# design.net
KiCad netlist of a schematic drawn in Altium Designer
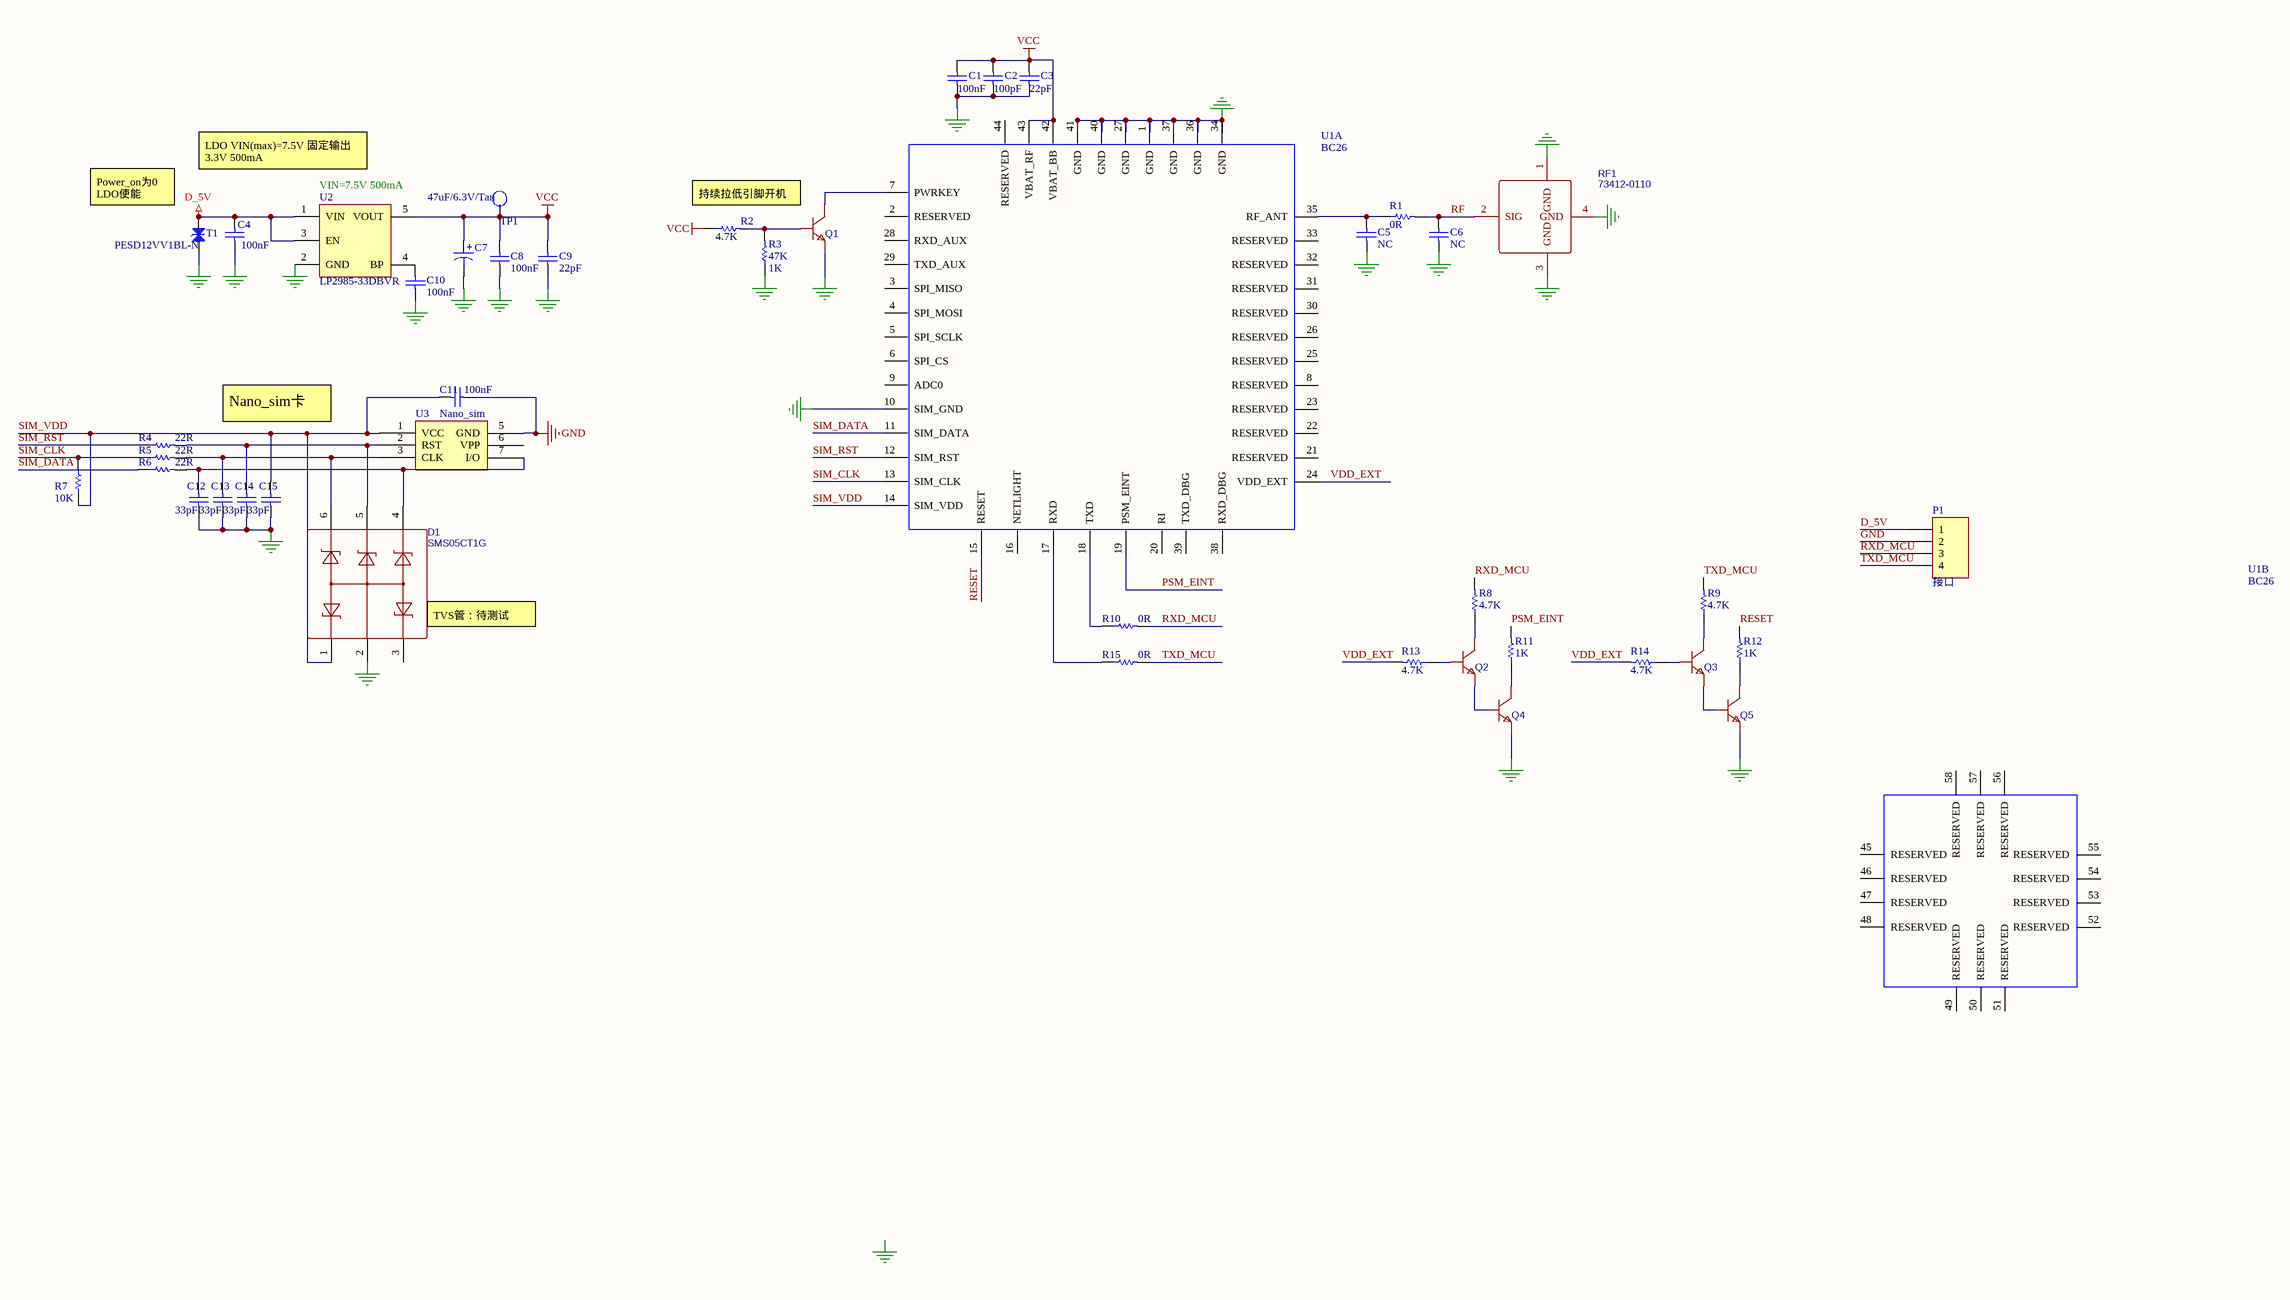
[diagram p0: 无线小样.SchDoc]

(export (version "E")
  (design (tool "Eeschema 10.0.6"))
  (components
    (comp (ref "C1")
      (value "100nF")
      (footprint "0402C")
      (description "Capacitor")
      (fields (field (name "PUBLISHER") "Altium Limited"))
      (libsource (lib "") (part "Cap_1"))
    )
    (comp (ref "C2")
      (value "100pF")
      (footprint "0402C")
      (description "Capacitor")
      (fields (field (name "PUBLISHER") "Altium Limited"))
      (libsource (lib "") (part "Cap_1"))
    )
    (comp (ref "C3")
      (value "22pF")
      (footprint "0402C")
      (description "Capacitor")
      (fields (field (name "PUBLISHER") "Altium Limited"))
      (libsource (lib "") (part "Cap_1"))
    )
    (comp (ref "C4")
      (value "100nF")
      (footprint "0402C")
      (description "Capacitor")
      (fields (field (name "PUBLISHER") "Altium Limited"))
      (libsource (lib "Miscellaneous Devices") (part "Cap"))
    )
    (comp (ref "C5")
      (value "NC")
      (footprint "0603C")
      (description "Capacitor")
      (fields (field (name "PUBLISHER") "Altium Limited"))
      (libsource (lib "") (part "Cap_1"))
    )
    (comp (ref "C6")
      (value "NC")
      (footprint "0603C")
      (description "Capacitor")
      (fields (field (name "PUBLISHER") "Altium Limited"))
      (libsource (lib "") (part "Cap_1"))
    )
    (comp (ref "C7")
      (value "47uF/6.3V/Tan")
      (footprint "0402C")
      (description "Polarized Capacitor (Radial)")
      (fields (field (name "PUBLISHER") "Altium Limited"))
      (libsource (lib "Miscellaneous Devices") (part "Cap Pol1"))
    )
    (comp (ref "C8")
      (value "100nF")
      (footprint "0402C")
      (description "Capacitor")
      (fields (field (name "PUBLISHER") "Altium Limited"))
      (libsource (lib "") (part "Cap_1"))
    )
    (comp (ref "C9")
      (value "22pF")
      (footprint "0402C")
      (description "Capacitor")
      (fields (field (name "PUBLISHER") "Altium Limited"))
      (libsource (lib "") (part "Cap_1"))
    )
    (comp (ref "C10")
      (value "100nF")
      (footprint "0402C")
      (description "Capacitor")
      (fields (field (name "PUBLISHER") "Altium Limited"))
      (libsource (lib "") (part "Cap_1"))
    )
    (comp (ref "C11")
      (value "100nF")
      (footprint "0402C")
      (description "Capacitor")
      (fields (field (name "PUBLISHER") "Altium Limited"))
      (libsource (lib "") (part "Cap_1"))
    )
    (comp (ref "C12")
      (value "33pF")
      (footprint "0402C")
      (description "Capacitor")
      (fields (field (name "PUBLISHER") "Altium Limited"))
      (libsource (lib "") (part "Cap_1"))
    )
    (comp (ref "C13")
      (value "33pF")
      (footprint "0402C")
      (description "Capacitor")
      (fields (field (name "PUBLISHER") "Altium Limited"))
      (libsource (lib "") (part "Cap_1"))
    )
    (comp (ref "C14")
      (value "33pF")
      (footprint "0402C")
      (description "Capacitor")
      (fields (field (name "PUBLISHER") "Altium Limited"))
      (libsource (lib "") (part "Cap_1"))
    )
    (comp (ref "C15")
      (value "33pF")
      (footprint "0402C")
      (description "Capacitor")
      (fields (field (name "PUBLISHER") "Altium Limited"))
      (libsource (lib "") (part "Cap_1"))
    )
    (comp (ref "D1")
      (value "SMS05CT1G")
      (footprint "TSOP-6_L3.0-W1.5-P0.95-LS2.8-BL")
      (fields (field (name "BOM_SUPPLIER PART") "C233427") (field (name "CONTRIBUTOR") "LCSC"))
      (libsource (lib "ESD") (part "SMS05CT1G"))
    )
    (comp (ref "P1")
      (value "接口")
      (footprint "HDR1X4")
      (description "Header, 4-Pin")
      (fields (field (name "PUBLISHER") "Altium Limited"))
      (libsource (lib "Miscellaneous Connectors") (part "Header 4"))
    )
    (comp (ref "Q1")
      (value "S8050-J3Y")
      (footprint "SOT23")
      (fields (field (name "BOM_SUPPLIER PART") "C364312") (field (name "CONTRIBUTOR") "LCSC"))
      (libsource (lib "npn") (part "S8050-J3Y"))
    )
    (comp (ref "Q2")
      (value "S8050-J3Y")
      (footprint "SOT23")
      (fields (field (name "BOM_SUPPLIER PART") "C364312") (field (name "CONTRIBUTOR") "LCSC"))
      (libsource (lib "npn") (part "S8050-J3Y"))
    )
    (comp (ref "Q3")
      (value "S8050-J3Y")
      (footprint "SOT23")
      (fields (field (name "BOM_SUPPLIER PART") "C364312") (field (name "CONTRIBUTOR") "LCSC"))
      (libsource (lib "npn") (part "S8050-J3Y"))
    )
    (comp (ref "Q4")
      (value "S8050-J3Y")
      (footprint "SOT23")
      (fields (field (name "BOM_SUPPLIER PART") "C364312") (field (name "CONTRIBUTOR") "LCSC"))
      (libsource (lib "npn") (part "S8050-J3Y"))
    )
    (comp (ref "Q5")
      (value "S8050-J3Y")
      (footprint "SOT23")
      (fields (field (name "BOM_SUPPLIER PART") "C364312") (field (name "CONTRIBUTOR") "LCSC"))
      (libsource (lib "npn") (part "S8050-J3Y"))
    )
    (comp (ref "R1")
      (value "0R")
      (footprint "0603R")
      (description "Resistor")
      (fields (field (name "PUBLISHER") "Altium Limited"))
      (libsource (lib "Miscellaneous Devices") (part "Res1"))
    )
    (comp (ref "R2")
      (value "4.7K")
      (footprint "0402R")
      (description "Resistor")
      (fields (field (name "PUBLISHER") "Altium Limited"))
      (libsource (lib "Miscellaneous Devices") (part "Res1"))
    )
    (comp (ref "R3")
      (value "47K")
      (footprint "0402R")
      (description "Resistor")
      (fields (field (name "ALTIUM_VALUE") "1K") (field (name "PUBLISHER") "Altium Limited"))
      (libsource (lib "Miscellaneous Devices") (part "Res1"))
    )
    (comp (ref "R4")
      (value "22R")
      (footprint "0402R")
      (description "Resistor")
      (fields (field (name "PUBLISHER") "Altium Limited"))
      (libsource (lib "Miscellaneous Devices") (part "Res1"))
    )
    (comp (ref "R5")
      (value "22R")
      (footprint "0402R")
      (description "Resistor")
      (fields (field (name "PUBLISHER") "Altium Limited"))
      (libsource (lib "Miscellaneous Devices") (part "Res1"))
    )
    (comp (ref "R6")
      (value "22R")
      (footprint "0402R")
      (description "Resistor")
      (fields (field (name "PUBLISHER") "Altium Limited"))
      (libsource (lib "Miscellaneous Devices") (part "Res1"))
    )
    (comp (ref "R7")
      (value "10K")
      (footprint "0402R")
      (description "Resistor")
      (fields (field (name "PUBLISHER") "Altium Limited"))
      (libsource (lib "Miscellaneous Devices") (part "Res1"))
    )
    (comp (ref "R8")
      (value "4.7K")
      (footprint "0402R")
      (description "Resistor")
      (fields (field (name "PUBLISHER") "Altium Limited"))
      (libsource (lib "Miscellaneous Devices") (part "Res1"))
    )
    (comp (ref "R9")
      (value "4.7K")
      (footprint "0402R")
      (description "Resistor")
      (fields (field (name "PUBLISHER") "Altium Limited"))
      (libsource (lib "Miscellaneous Devices") (part "Res1"))
    )
    (comp (ref "R10")
      (value "0R")
      (footprint "0402R")
      (description "Resistor")
      (fields (field (name "PUBLISHER") "Altium Limited"))
      (libsource (lib "Miscellaneous Devices") (part "Res1"))
    )
    (comp (ref "R11")
      (value "1K")
      (footprint "0402R")
      (description "Resistor")
      (fields (field (name "PUBLISHER") "Altium Limited"))
      (libsource (lib "Miscellaneous Devices") (part "Res1"))
    )
    (comp (ref "R12")
      (value "1K")
      (footprint "0402R")
      (description "Resistor")
      (fields (field (name "PUBLISHER") "Altium Limited"))
      (libsource (lib "Miscellaneous Devices") (part "Res1"))
    )
    (comp (ref "R13")
      (value "4.7K")
      (footprint "0402R")
      (description "Resistor")
      (fields (field (name "PUBLISHER") "Altium Limited"))
      (libsource (lib "Miscellaneous Devices") (part "Res1"))
    )
    (comp (ref "R14")
      (value "4.7K")
      (footprint "0402R")
      (description "Resistor")
      (fields (field (name "PUBLISHER") "Altium Limited"))
      (libsource (lib "Miscellaneous Devices") (part "Res1"))
    )
    (comp (ref "R15")
      (value "0R")
      (footprint "0402R")
      (description "Resistor")
      (fields (field (name "PUBLISHER") "Altium Limited"))
      (libsource (lib "Miscellaneous Devices") (part "Res1"))
    )
    (comp (ref "RF1")
      (value "73412-0110")
      (footprint "ANT-SMD_73412-0110")
      (fields (field (name "BOM_SUPPLIER PART") "C434806") (field (name "CONTRIBUTOR") "LCSC"))
      (libsource (lib "RF") (part "73412-0110"))
    )
    (comp (ref "T1")
      (value "PESD12VV1BL-N")
      (footprint "X1-DFN1006-2_L1.0-W0.6-RD")
      (libsource (lib "mySchlib") (part "TVS2"))
    )
    (comp (ref "TP1")
      (value "Testpoint")
      (footprint "General:TP")
      (libsource (lib "mySchlib") (part "Testpoint"))
    )
    (comp (ref "U1") (value "BC26") (footprint "BC26") (libsource (lib "") (part "BC26_1")))
    (comp (ref "U2")
      (value "LP2985-33DBVR")
      (footprint "SOT-23-5")
      (libsource (lib "mySchlib") (part "SGM2019"))
    )
    (comp (ref "U3") (value "Nano_sim") (footprint "SIM-SMD_C77877") (libsource (lib "测试") (part "Nano_sim")))
  )
  (nets
    (net (code "1") (name "/PSM_EINT") (class "Default")
      (node (ref "R11") (pin "2") (pinfunction "2_2") (pintype "passive"))
      (node (ref "U1") (pin "19") (pinfunction "PSM_EINT_19") (pintype "passive"))
    )
    (net (code "2") (name "/RESET") (class "Default")
      (node (ref "R12") (pin "2") (pinfunction "2_2") (pintype "passive"))
      (node (ref "U1") (pin "15") (pinfunction "RESET_15") (pintype "passive"))
    )
    (net (code "3") (name "/RF") (class "Default")
      (node (ref "C6") (pin "2") (pinfunction "2_2") (pintype "passive"))
      (node (ref "R1") (pin "2") (pinfunction "2_2") (pintype "passive"))
      (node (ref "RF1") (pin "2") (pinfunction "SIG_2") (pintype "passive"))
    )
    (net (code "4") (name "/RXD_MCU") (class "Default")
      (node (ref "P1") (pin "3") (pinfunction "3_3") (pintype "passive"))
      (node (ref "R10") (pin "2") (pinfunction "2_2") (pintype "passive"))
      (node (ref "R8") (pin "2") (pinfunction "2_2") (pintype "passive"))
    )
    (net (code "5") (name "/SIM_CLK") (class "Default")
      (node (ref "R5") (pin "1") (pinfunction "1_1") (pintype "passive"))
      (node (ref "R7") (pin "2") (pinfunction "2_2") (pintype "passive"))
      (node (ref "U1") (pin "13") (pinfunction "SIM_CLK_13") (pintype "passive"))
    )
    (net (code "6") (name "/SIM_DATA") (class "Default")
      (node (ref "R6") (pin "1") (pinfunction "1_1") (pintype "passive"))
      (node (ref "U1") (pin "11") (pinfunction "SIM_DATA_11") (pintype "passive"))
    )
    (net (code "7") (name "/SIM_RST") (class "Default")
      (node (ref "R4") (pin "1") (pinfunction "1_1") (pintype "passive"))
      (node (ref "U1") (pin "12") (pinfunction "SIM_RST_12") (pintype "passive"))
    )
    (net (code "8") (name "/SIM_VDD") (class "Default")
      (node (ref "C11") (pin "1") (pinfunction "1_1") (pintype "passive"))
      (node (ref "C15") (pin "2") (pinfunction "2_2") (pintype "passive"))
      (node (ref "D1") (pin "1") (pinfunction "1_1") (pintype "passive"))
      (node (ref "R7") (pin "1") (pinfunction "1_1") (pintype "passive"))
      (node (ref "U1") (pin "14") (pinfunction "SIM_VDD_14") (pintype "passive"))
      (node (ref "U3") (pin "1") (pinfunction "VCC_1") (pintype "passive"))
    )
    (net (code "9") (name "/TXD_MCU") (class "Default")
      (node (ref "P1") (pin "4") (pinfunction "4_4") (pintype "passive"))
      (node (ref "R15") (pin "2") (pinfunction "2_2") (pintype "passive"))
      (node (ref "R9") (pin "2") (pinfunction "2_2") (pintype "passive"))
    )
    (net (code "10") (name "/VDD_EXT") (class "Default")
      (node (ref "R13") (pin "2") (pinfunction "2_2") (pintype "passive"))
      (node (ref "R14") (pin "2") (pinfunction "2_2") (pintype "passive"))
      (node (ref "U1") (pin "24") (pinfunction "VDD_EXT_24") (pintype "passive"))
    )
    (net (code "11") (name "D_5V") (class "Default")
      (node (ref "C4") (pin "1") (pinfunction "1_1") (pintype "passive"))
      (node (ref "P1") (pin "1") (pinfunction "1_1") (pintype "passive"))
      (node (ref "T1") (pin "2") (pinfunction "2_2") (pintype "passive"))
      (node (ref "U2") (pin "1") (pinfunction "VIN_1") (pintype "passive"))
      (node (ref "U2") (pin "3") (pinfunction "EN_3") (pintype "passive"))
    )
    (net (code "12") (name "GND") (class "Default")
      (node (ref "C1") (pin "1") (pinfunction "1_1") (pintype "passive"))
      (node (ref "C10") (pin "1") (pinfunction "1_1") (pintype "passive"))
      (node (ref "C11") (pin "2") (pinfunction "2_2") (pintype "passive"))
      (node (ref "C12") (pin "1") (pinfunction "1_1") (pintype "passive"))
      (node (ref "C13") (pin "1") (pinfunction "1_1") (pintype "passive"))
      (node (ref "C14") (pin "1") (pinfunction "1_1") (pintype "passive"))
      (node (ref "C15") (pin "1") (pinfunction "1_1") (pintype "passive"))
      (node (ref "C2") (pin "1") (pinfunction "1_1") (pintype "passive"))
      (node (ref "C3") (pin "1") (pinfunction "1_1") (pintype "passive"))
      (node (ref "C4") (pin "2") (pinfunction "2_2") (pintype "passive"))
      (node (ref "C5") (pin "1") (pinfunction "1_1") (pintype "passive"))
      (node (ref "C6") (pin "1") (pinfunction "1_1") (pintype "passive"))
      (node (ref "C7") (pin "2") (pinfunction "2_2") (pintype "passive"))
      (node (ref "C8") (pin "1") (pinfunction "1_1") (pintype "passive"))
      (node (ref "C9") (pin "1") (pinfunction "1_1") (pintype "passive"))
      (node (ref "D1") (pin "2") (pinfunction "2_2") (pintype "passive"))
      (node (ref "P1") (pin "2") (pinfunction "2_2") (pintype "passive"))
      (node (ref "Q1") (pin "2") (pinfunction "E_2") (pintype "passive"))
      (node (ref "Q4") (pin "2") (pinfunction "E_2") (pintype "passive"))
      (node (ref "Q5") (pin "2") (pinfunction "E_2") (pintype "passive"))
      (node (ref "R3") (pin "1") (pinfunction "1_1") (pintype "passive"))
      (node (ref "RF1") (pin "1") (pinfunction "GND_1") (pintype "passive"))
      (node (ref "RF1") (pin "3") (pinfunction "GND_3") (pintype "passive"))
      (node (ref "RF1") (pin "4") (pinfunction "GND_4") (pintype "passive"))
      (node (ref "T1") (pin "1") (pinfunction "1_1") (pintype "passive"))
      (node (ref "U1") (pin "1") (pinfunction "GND_1") (pintype "passive"))
      (node (ref "U1") (pin "10") (pinfunction "SIM_GND_10") (pintype "passive"))
      (node (ref "U1") (pin "27") (pinfunction "GND_27") (pintype "passive"))
      (node (ref "U1") (pin "34") (pinfunction "GND_34") (pintype "passive"))
      (node (ref "U1") (pin "36") (pinfunction "GND_36") (pintype "passive"))
      (node (ref "U1") (pin "37") (pinfunction "GND_37") (pintype "passive"))
      (node (ref "U1") (pin "40") (pinfunction "GND_40") (pintype "passive"))
      (node (ref "U1") (pin "41") (pinfunction "GND_41") (pintype "passive"))
      (node (ref "U2") (pin "2") (pinfunction "GND_2") (pintype "passive"))
      (node (ref "U3") (pin "5") (pinfunction "GND_5") (pintype "passive"))
    )
    (net (code "13") (name "Net-(Q1-B)") (class "Default")
      (node (ref "Q1") (pin "1") (pinfunction "B_1") (pintype "passive"))
      (node (ref "R2") (pin "2") (pinfunction "2_2") (pintype "passive"))
      (node (ref "R3") (pin "2") (pinfunction "2_2") (pintype "passive"))
    )
    (net (code "14") (name "Net-(Q1-C)") (class "Default")
      (node (ref "Q1") (pin "3") (pinfunction "C_3") (pintype "passive"))
      (node (ref "U1") (pin "7") (pinfunction "PWRKEY_7") (pintype "passive"))
    )
    (net (code "15") (name "Net-(Q2-B)") (class "Default")
      (node (ref "Q2") (pin "1") (pinfunction "B_1") (pintype "passive"))
      (node (ref "R13") (pin "1") (pinfunction "1_1") (pintype "passive"))
    )
    (net (code "16") (name "Net-(Q2-C)") (class "Default")
      (node (ref "Q2") (pin "3") (pinfunction "C_3") (pintype "passive"))
      (node (ref "R8") (pin "1") (pinfunction "1_1") (pintype "passive"))
    )
    (net (code "17") (name "Net-(Q2-E)") (class "Default")
      (node (ref "Q2") (pin "2") (pinfunction "E_2") (pintype "passive"))
      (node (ref "Q4") (pin "1") (pinfunction "B_1") (pintype "passive"))
    )
    (net (code "18") (name "Net-(Q3-B)") (class "Default")
      (node (ref "Q3") (pin "1") (pinfunction "B_1") (pintype "passive"))
      (node (ref "R14") (pin "1") (pinfunction "1_1") (pintype "passive"))
    )
    (net (code "19") (name "Net-(Q3-C)") (class "Default")
      (node (ref "Q3") (pin "3") (pinfunction "C_3") (pintype "passive"))
      (node (ref "R9") (pin "1") (pinfunction "1_1") (pintype "passive"))
    )
    (net (code "20") (name "Net-(Q3-E)") (class "Default")
      (node (ref "Q3") (pin "2") (pinfunction "E_2") (pintype "passive"))
      (node (ref "Q5") (pin "1") (pinfunction "B_1") (pintype "passive"))
    )
    (net (code "21") (name "Net-(Q4-C)") (class "Default")
      (node (ref "Q4") (pin "3") (pinfunction "C_3") (pintype "passive"))
      (node (ref "R11") (pin "1") (pinfunction "1_1") (pintype "passive"))
    )
    (net (code "22") (name "Net-(Q5-C)") (class "Default")
      (node (ref "Q5") (pin "3") (pinfunction "C_3") (pintype "passive"))
      (node (ref "R12") (pin "1") (pinfunction "1_1") (pintype "passive"))
    )
    (net (code "23") (name "Net-(U1A-RF_ANT)") (class "Default")
      (node (ref "C5") (pin "2") (pinfunction "2_2") (pintype "passive"))
      (node (ref "R1") (pin "1") (pinfunction "1_1") (pintype "passive"))
      (node (ref "U1") (pin "35") (pinfunction "RF_ANT_35") (pintype "passive"))
    )
    (net (code "24") (name "Net-(U1A-RXD)") (class "Default")
      (node (ref "R15") (pin "1") (pinfunction "1_1") (pintype "passive"))
      (node (ref "U1") (pin "17") (pinfunction "RXD_17") (pintype "passive"))
    )
    (net (code "25") (name "Net-(U1A-TXD)") (class "Default")
      (node (ref "R10") (pin "1") (pinfunction "1_1") (pintype "passive"))
      (node (ref "U1") (pin "18") (pinfunction "TXD_18") (pintype "passive"))
    )
    (net (code "26") (name "Net-(U2-BP)") (class "Default")
      (node (ref "C10") (pin "2") (pinfunction "2_2") (pintype "passive"))
      (node (ref "U2") (pin "4") (pinfunction "BP_4") (pintype "passive"))
    )
    (net (code "27") (name "Net-(U3-CLK)") (class "Default")
      (node (ref "C13") (pin "2") (pinfunction "2_2") (pintype "passive"))
      (node (ref "D1") (pin "6") (pinfunction "6_6") (pintype "passive"))
      (node (ref "R5") (pin "2") (pinfunction "2_2") (pintype "passive"))
      (node (ref "U3") (pin "3") (pinfunction "CLK_3") (pintype "passive"))
    )
    (net (code "28") (name "Net-(U3-I{slash}O)") (class "Default")
      (node (ref "C12") (pin "2") (pinfunction "2_2") (pintype "passive"))
      (node (ref "D1") (pin "4") (pinfunction "4_4") (pintype "passive"))
      (node (ref "R6") (pin "2") (pinfunction "2_2") (pintype "passive"))
      (node (ref "U3") (pin "7") (pinfunction "I/O_7") (pintype "passive"))
    )
    (net (code "29") (name "Net-(U3-RST)") (class "Default")
      (node (ref "C14") (pin "2") (pinfunction "2_2") (pintype "passive"))
      (node (ref "D1") (pin "5") (pinfunction "5_5") (pintype "passive"))
      (node (ref "R4") (pin "2") (pinfunction "2_2") (pintype "passive"))
      (node (ref "U3") (pin "2") (pinfunction "RST_2") (pintype "passive"))
    )
    (net (code "30") (name "VCC") (class "Default")
      (node (ref "C1") (pin "2") (pinfunction "2_2") (pintype "passive"))
      (node (ref "C2") (pin "2") (pinfunction "2_2") (pintype "passive"))
      (node (ref "C3") (pin "2") (pinfunction "2_2") (pintype "passive"))
      (node (ref "C7") (pin "1") (pinfunction "1_1") (pintype "passive"))
      (node (ref "C8") (pin "2") (pinfunction "2_2") (pintype "passive"))
      (node (ref "C9") (pin "2") (pinfunction "2_2") (pintype "passive"))
      (node (ref "R2") (pin "1") (pinfunction "1_1") (pintype "passive"))
      (node (ref "TP1") (pin "1") (pinfunction "1_1") (pintype "passive"))
      (node (ref "U1") (pin "42") (pinfunction "VBAT_BB_42") (pintype "passive"))
      (node (ref "U1") (pin "43") (pinfunction "VBAT_RF_43") (pintype "passive"))
      (node (ref "U2") (pin "5") (pinfunction "VOUT_5") (pintype "passive"))
    )
    (net (code "31") (name "unconnected-(D1-Pad3)") (class "Default")
      (node (ref "D1") (pin "3") (pinfunction "3_3") (pintype "passive"))
    )
    (net (code "32") (name "unconnected-(U1A-ADC0-Pad9)") (class "Default")
      (node (ref "U1") (pin "9") (pinfunction "ADC0_9") (pintype "passive"))
    )
    (net (code "33") (name "unconnected-(U1A-NETLIGHT-Pad16)") (class "Default")
      (node (ref "U1") (pin "16") (pinfunction "NETLIGHT_16") (pintype "passive"))
    )
    (net (code "34") (name "unconnected-(U1A-RESERVED-Pad2)") (class "Default")
      (node (ref "U1") (pin "2") (pinfunction "RESERVED_2") (pintype "passive"))
    )
    (net (code "35") (name "unconnected-(U1A-RESERVED-Pad8)") (class "Default")
      (node (ref "U1") (pin "8") (pinfunction "RESERVED_8") (pintype "passive"))
    )
    (net (code "36") (name "unconnected-(U1A-RESERVED-Pad21)") (class "Default")
      (node (ref "U1") (pin "21") (pinfunction "RESERVED_21") (pintype "passive"))
    )
    (net (code "37") (name "unconnected-(U1A-RESERVED-Pad22)") (class "Default")
      (node (ref "U1") (pin "22") (pinfunction "RESERVED_22") (pintype "passive"))
    )
    (net (code "38") (name "unconnected-(U1A-RESERVED-Pad23)") (class "Default")
      (node (ref "U1") (pin "23") (pinfunction "RESERVED_23") (pintype "passive"))
    )
    (net (code "39") (name "unconnected-(U1A-RESERVED-Pad25)") (class "Default")
      (node (ref "U1") (pin "25") (pinfunction "RESERVED_25") (pintype "passive"))
    )
    (net (code "40") (name "unconnected-(U1A-RESERVED-Pad26)") (class "Default")
      (node (ref "U1") (pin "26") (pinfunction "RESERVED_26") (pintype "passive"))
    )
    (net (code "41") (name "unconnected-(U1A-RESERVED-Pad30)") (class "Default")
      (node (ref "U1") (pin "30") (pinfunction "RESERVED_30") (pintype "passive"))
    )
    (net (code "42") (name "unconnected-(U1A-RESERVED-Pad31)") (class "Default")
      (node (ref "U1") (pin "31") (pinfunction "RESERVED_31") (pintype "passive"))
    )
    (net (code "43") (name "unconnected-(U1A-RESERVED-Pad32)") (class "Default")
      (node (ref "U1") (pin "32") (pinfunction "RESERVED_32") (pintype "passive"))
    )
    (net (code "44") (name "unconnected-(U1A-RESERVED-Pad33)") (class "Default")
      (node (ref "U1") (pin "33") (pinfunction "RESERVED_33") (pintype "passive"))
    )
    (net (code "45") (name "unconnected-(U1A-RESERVED-Pad44)") (class "Default")
      (node (ref "U1") (pin "44") (pinfunction "RESERVED_44") (pintype "passive"))
    )
    (net (code "46") (name "unconnected-(U1A-RI-Pad20)") (class "Default")
      (node (ref "U1") (pin "20") (pinfunction "RI_20") (pintype "passive"))
    )
    (net (code "47") (name "unconnected-(U1A-RXD_AUX-Pad28)") (class "Default")
      (node (ref "U1") (pin "28") (pinfunction "RXD_AUX_28") (pintype "passive"))
    )
    (net (code "48") (name "unconnected-(U1A-RXD_DBG-Pad38)") (class "Default")
      (node (ref "U1") (pin "38") (pinfunction "RXD_DBG_38") (pintype "passive"))
    )
    (net (code "49") (name "unconnected-(U1A-SPI_CS-Pad6)") (class "Default")
      (node (ref "U1") (pin "6") (pinfunction "SPI_CS_6") (pintype "passive"))
    )
    (net (code "50") (name "unconnected-(U1A-SPI_MISO-Pad3)") (class "Default")
      (node (ref "U1") (pin "3") (pinfunction "SPI_MISO_3") (pintype "passive"))
    )
    (net (code "51") (name "unconnected-(U1A-SPI_MOSI-Pad4)") (class "Default")
      (node (ref "U1") (pin "4") (pinfunction "SPI_MOSI_4") (pintype "passive"))
    )
    (net (code "52") (name "unconnected-(U1A-SPI_SCLK-Pad5)") (class "Default")
      (node (ref "U1") (pin "5") (pinfunction "SPI_SCLK_5") (pintype "passive"))
    )
    (net (code "53") (name "unconnected-(U1A-TXD_AUX-Pad29)") (class "Default")
      (node (ref "U1") (pin "29") (pinfunction "TXD_AUX_29") (pintype "passive"))
    )
    (net (code "54") (name "unconnected-(U1A-TXD_DBG-Pad39)") (class "Default")
      (node (ref "U1") (pin "39") (pinfunction "TXD_DBG_39") (pintype "passive"))
    )
    (net (code "55") (name "unconnected-(U1B-RESERVED-Pad45)") (class "Default")
      (node (ref "U1") (pin "45") (pinfunction "RESERVED_45") (pintype "passive"))
    )
    (net (code "56") (name "unconnected-(U1B-RESERVED-Pad46)") (class "Default")
      (node (ref "U1") (pin "46") (pinfunction "RESERVED_46") (pintype "passive"))
    )
    (net (code "57") (name "unconnected-(U1B-RESERVED-Pad47)") (class "Default")
      (node (ref "U1") (pin "47") (pinfunction "RESERVED_47") (pintype "passive"))
    )
    (net (code "58") (name "unconnected-(U1B-RESERVED-Pad48)") (class "Default")
      (node (ref "U1") (pin "48") (pinfunction "RESERVED_48") (pintype "passive"))
    )
    (net (code "59") (name "unconnected-(U1B-RESERVED-Pad49)") (class "Default")
      (node (ref "U1") (pin "49") (pinfunction "RESERVED_49") (pintype "passive"))
    )
    (net (code "60") (name "unconnected-(U1B-RESERVED-Pad50)") (class "Default")
      (node (ref "U1") (pin "50") (pinfunction "RESERVED_50") (pintype "passive"))
    )
    (net (code "61") (name "unconnected-(U1B-RESERVED-Pad51)") (class "Default")
      (node (ref "U1") (pin "51") (pinfunction "RESERVED_51") (pintype "passive"))
    )
    (net (code "62") (name "unconnected-(U1B-RESERVED-Pad52)") (class "Default")
      (node (ref "U1") (pin "52") (pinfunction "RESERVED_52") (pintype "passive"))
    )
    (net (code "63") (name "unconnected-(U1B-RESERVED-Pad53)") (class "Default")
      (node (ref "U1") (pin "53") (pinfunction "RESERVED_53") (pintype "passive"))
    )
    (net (code "64") (name "unconnected-(U1B-RESERVED-Pad54)") (class "Default")
      (node (ref "U1") (pin "54") (pinfunction "RESERVED_54") (pintype "passive"))
    )
    (net (code "65") (name "unconnected-(U1B-RESERVED-Pad55)") (class "Default")
      (node (ref "U1") (pin "55") (pinfunction "RESERVED_55") (pintype "passive"))
    )
    (net (code "66") (name "unconnected-(U1B-RESERVED-Pad56)") (class "Default")
      (node (ref "U1") (pin "56") (pinfunction "RESERVED_56") (pintype "passive"))
    )
    (net (code "67") (name "unconnected-(U1B-RESERVED-Pad57)") (class "Default")
      (node (ref "U1") (pin "57") (pinfunction "RESERVED_57") (pintype "passive"))
    )
    (net (code "68") (name "unconnected-(U1B-RESERVED-Pad58)") (class "Default")
      (node (ref "U1") (pin "58") (pinfunction "RESERVED_58") (pintype "passive"))
    )
    (net (code "69") (name "unconnected-(U3-VPP-Pad6)") (class "Default")
      (node (ref "U3") (pin "6") (pinfunction "VPP_6") (pintype "passive"))
    )
  )
)
